# ADIS_Teensy_Arduino_Breakout_RevC.net
KiCad netlist of a schematic drawn in EAGLE
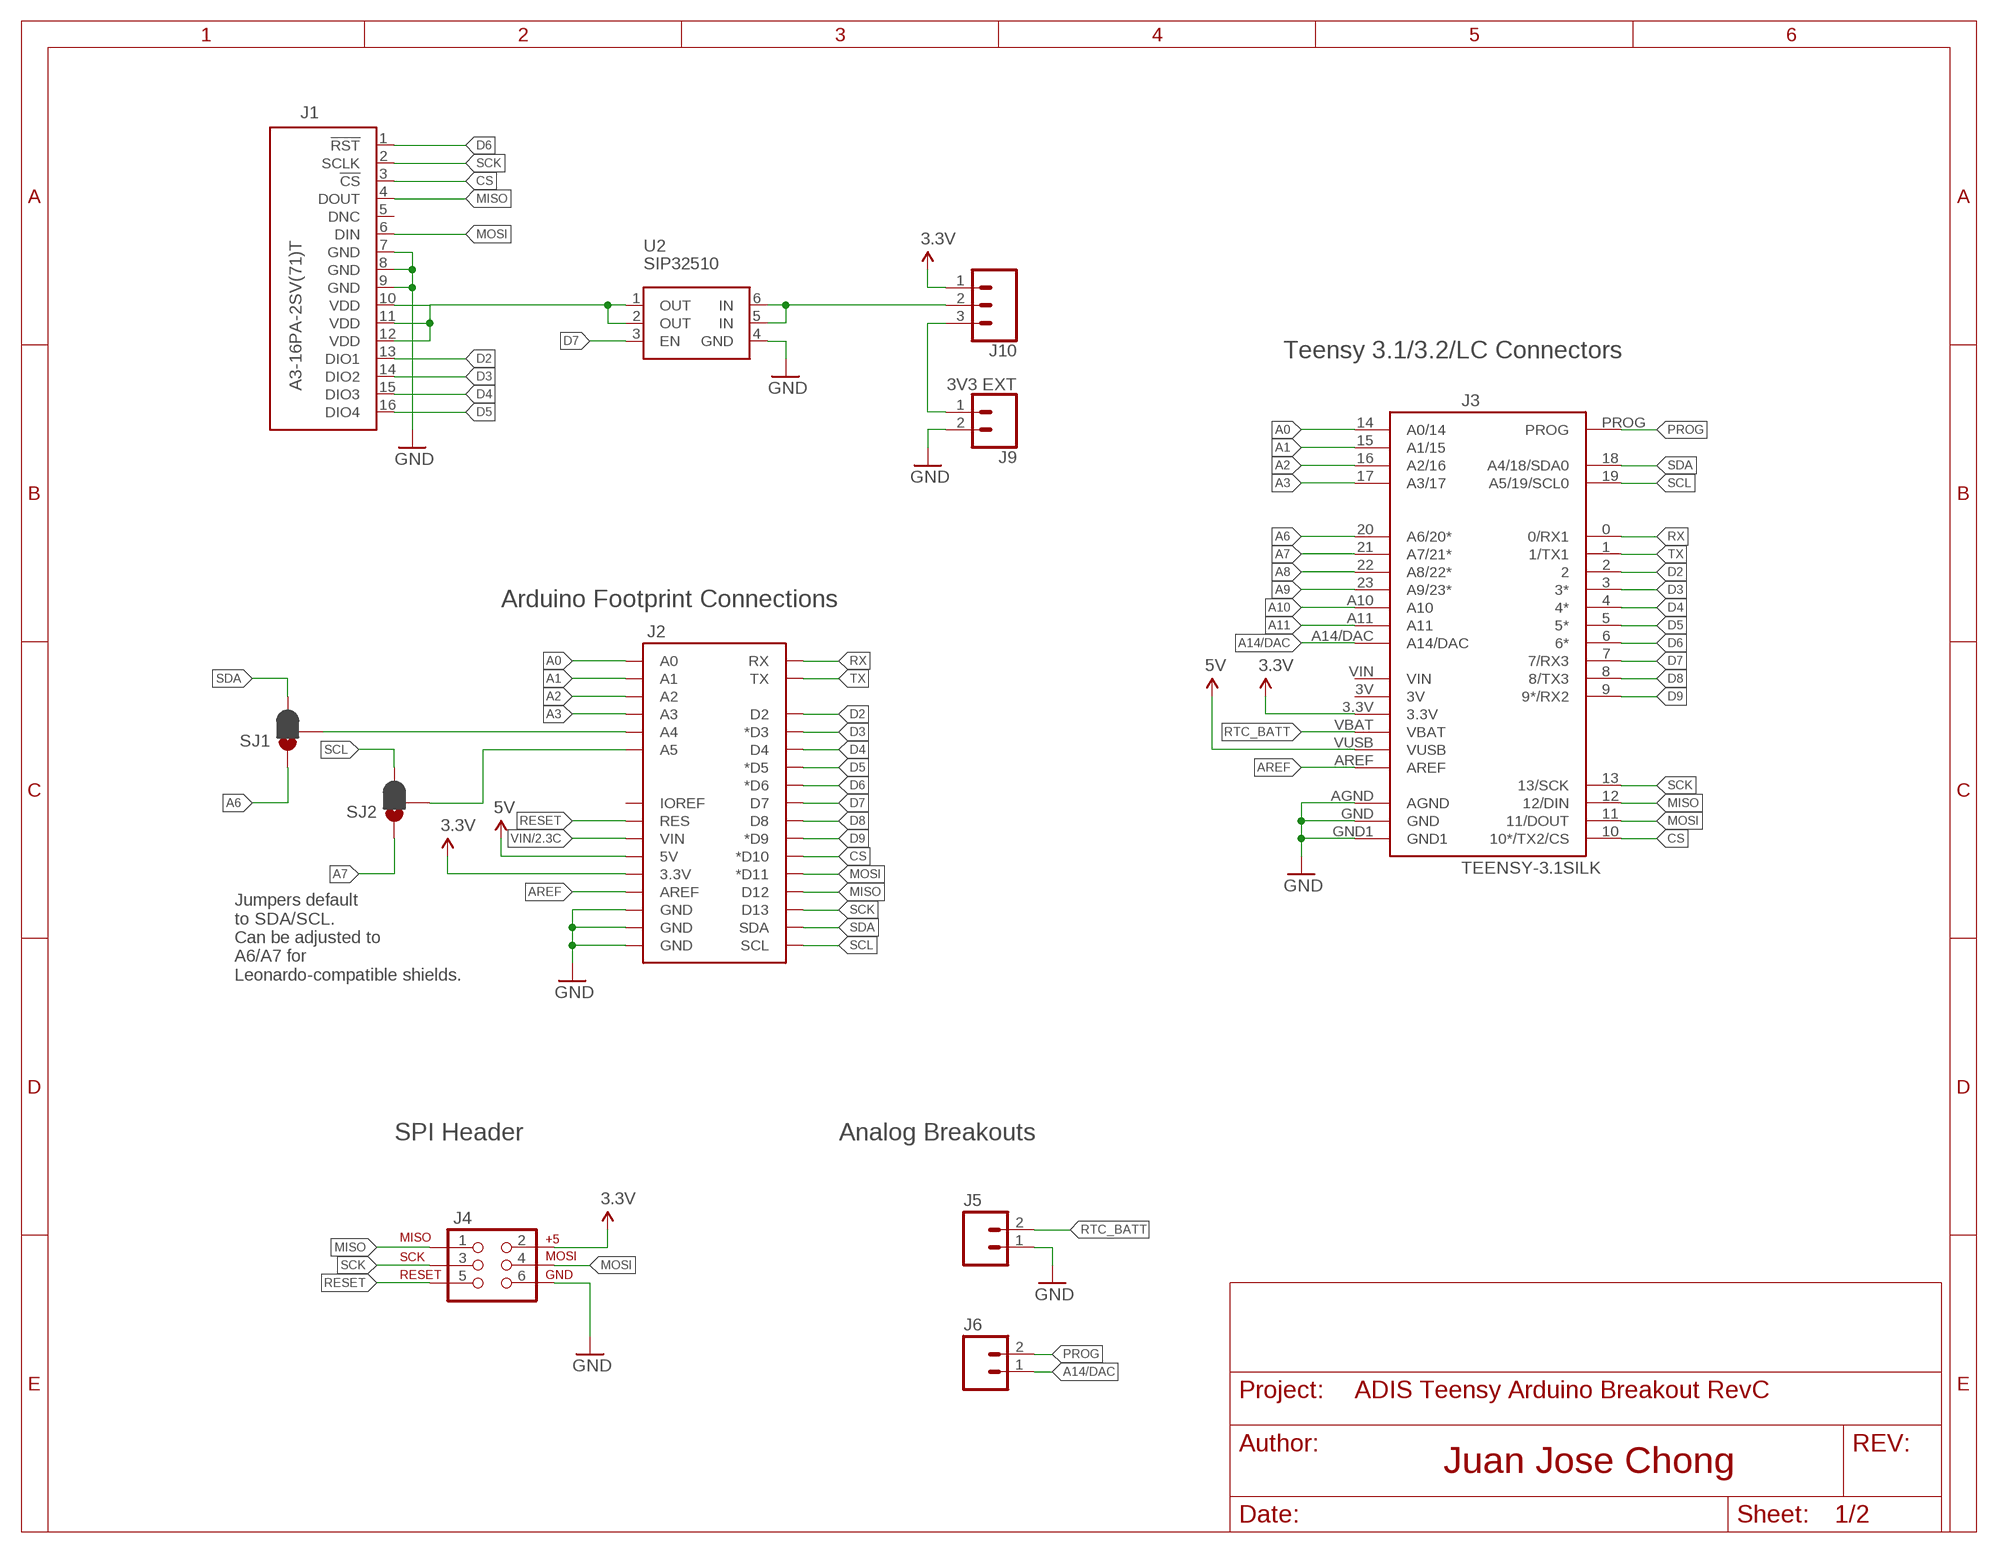
[diagram p0: schematic, sheet 1]
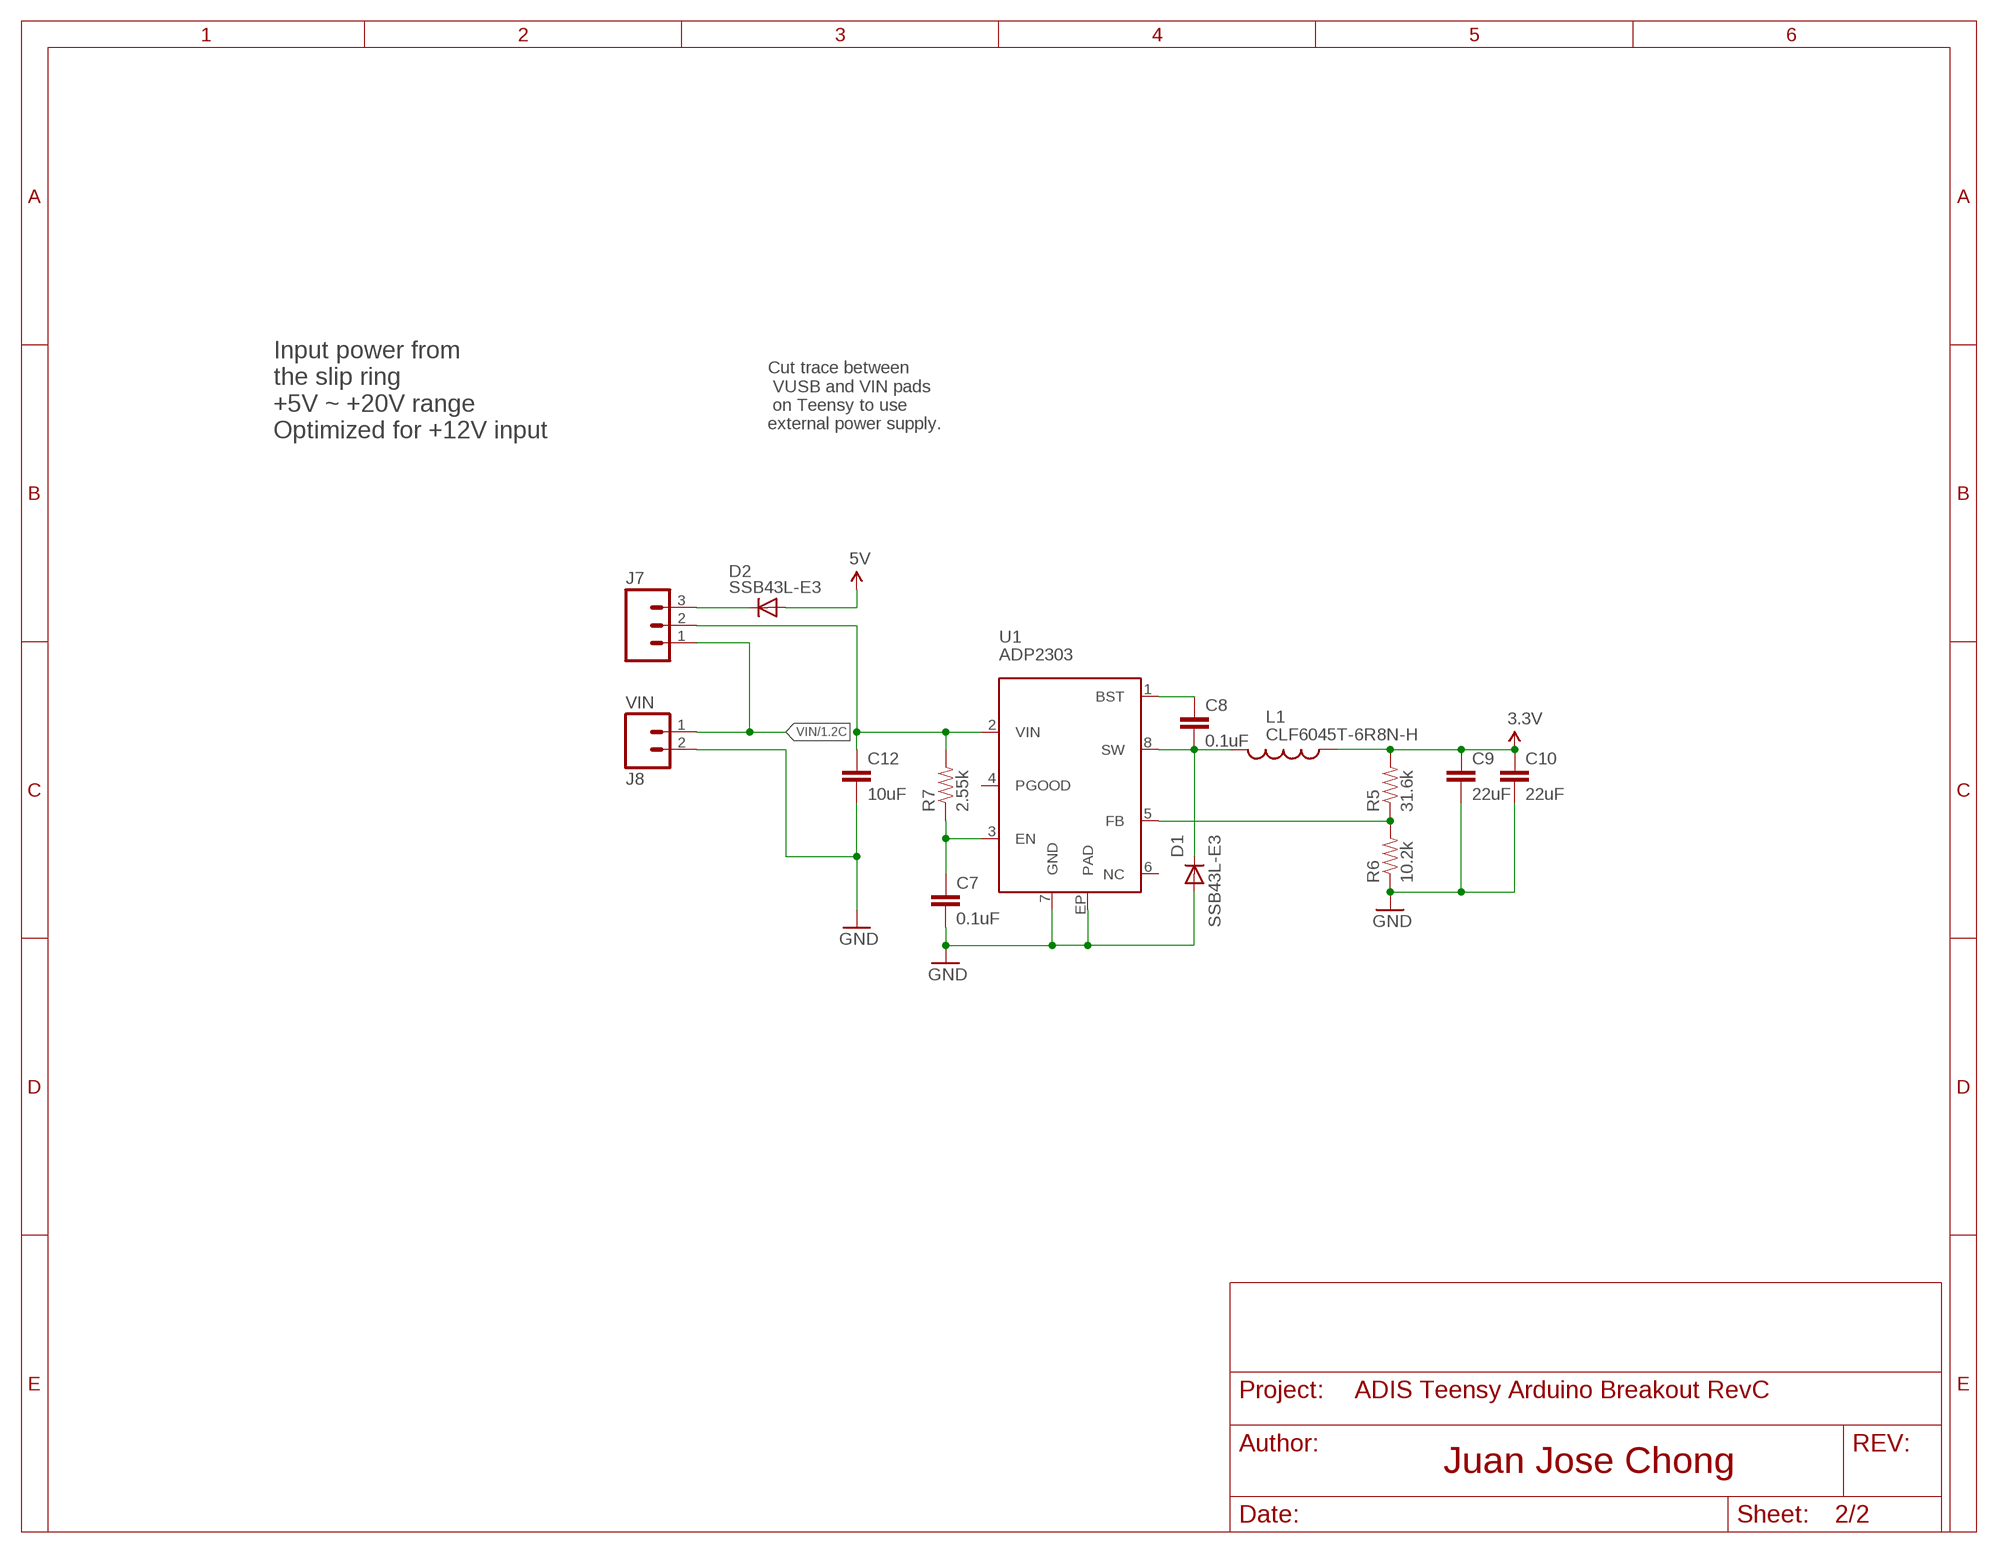
[diagram p1: schematic, sheet 2]

(export (version "E")
  (design (tool "Eeschema 10.0.6"))
  (components
    (comp (ref "C7")
      (value "0.1uF")
      (footprint "eagle-import:0603-CAP")
      (fields (field (name "PARTNO") "CL10B104KB8NNNC"))
      (libsource (lib "eagle-import") (part "CAP0603-CAP"))
    )
    (comp (ref "C8")
      (value "0.1uF")
      (footprint "eagle-import:0603-CAP")
      (fields (field (name "PARTNO") "CL10B104KB8NNNC"))
      (libsource (lib "eagle-import") (part "CAP0603-CAP"))
    )
    (comp (ref "C9")
      (value "22uF")
      (footprint "eagle-import:1210")
      (fields (field (name "PARTNO") "TLJA476M010R0600"))
      (libsource (lib "eagle-import") (part "CAP1210"))
    )
    (comp (ref "C10")
      (value "22uF")
      (footprint "eagle-import:1210")
      (fields (field (name "PARTNO") "TLJA476M010R0600"))
      (libsource (lib "eagle-import") (part "CAP1210"))
    )
    (comp (ref "C12")
      (value "10uF")
      (footprint "eagle-import:1206")
      (fields (field (name "PARTNO") "TLJA476M010R0600"))
      (libsource (lib "eagle-import") (part "CAP1206"))
    )
    (comp (ref "D1")
      (value "SSB43L-E3")
      (footprint "eagle-import:DO214AA")
      (fields (field (name "PARTNO") "SSB43L-E3/52T"))
      (libsource (lib "eagle-import") (part "DIODE-DO214AA"))
    )
    (comp (ref "D2")
      (value "SSB43L-E3")
      (footprint "eagle-import:DO214AA")
      (fields (field (name "PARTNO") "SSB43L-E3/52T"))
      (libsource (lib "eagle-import") (part "DIODE-DO214AA"))
    )
    (comp (ref "J7")
      (value "M03PTH")
      (footprint "eagle-import:1X03@1")
      (fields (field (name "PARTNO") "68000-103HLF"))
      (libsource (lib "eagle-import") (part "M03PTH"))
    )
    (comp (ref "J8")
      (value "VIN")
      (footprint "eagle-import:SCREWTERMINAL-3.5MM-2@1")
      (fields (field (name "PARTNO") "20020327-C021B01LF"))
      (libsource (lib "eagle-import") (part "M023.5MM"))
    )
    (comp (ref "L1")
      (value "CLF6045T-6R8N-H")
      (footprint "eagle-import:CLF6045-H")
      (libsource (lib "eagle-import") (part "CLF6045T-6R8N-H"))
    )
    (comp (ref "R5")
      (value "31.6k")
      (footprint "eagle-import:0603-RES")
      (fields (field (name "PARTNO") "ERJ-3EKF3162V"))
      (libsource (lib "eagle-import") (part "RESISTOR0603-RES"))
    )
    (comp (ref "R6")
      (value "10.2k")
      (footprint "eagle-import:0603-RES")
      (fields (field (name "PARTNO") "ERJ-3EKF1022V"))
      (libsource (lib "eagle-import") (part "RESISTOR0603-RES"))
    )
    (comp (ref "R7")
      (value "2.55k")
      (footprint "eagle-import:0603-RES")
      (fields (field (name "PARTNO") "ERJ-3EKF2551V"))
      (libsource (lib "eagle-import") (part "RESISTOR0603-RES"))
    )
    (comp (ref "U1")
      (value "ADP2303")
      (footprint "eagle-import:SOIC-8-PAD")
      (fields (field (name "PARTNO") "ADP2303ARDZ"))
      (libsource (lib "eagle-import") (part "ADP2303"))
    )
    (comp (ref "J1")
      (value "A3-16PA-2SV(71)T")
      (footprint "eagle-import:A3-16PA-2SV(71)-TOP")
      (fields (field (name "PARTNO") "A3-16PA-2SV(71)"))
      (libsource (lib "eagle-import") (part "A3-16PA-2SV(71)T"))
    )
    (comp (ref "J2")
      (value "ARDUINO_R3_SHIELDUNO_R3_SHIELD_HOLES")
      (footprint "eagle-import:UNO_R3_SHIELD_HOLES")
      (libsource (lib "eagle-import") (part "ARDUINO_R3_SHIELDUNO_R3_SHIELD_HOLES"))
    )
    (comp (ref "J3")
      (value "TEENSY-3.1SILK")
      (footprint "eagle-import:TEENSY-3.1")
      (fields (field (name "PARTNO") "TEENSY32"))
      (libsource (lib "eagle-import") (part "TEENSY-3.1SILK"))
    )
    (comp (ref "J4")
      (value "AVR_SPI_PRG_6PTH")
      (footprint "eagle-import:2X3")
      (fields (field (name "PARTNO") "M20-9720345"))
      (libsource (lib "eagle-import") (part "AVR_SPI_PRG_6PTH"))
    )
    (comp (ref "J5")
      (value "M02PTH")
      (footprint "eagle-import:1X02@1")
      (libsource (lib "eagle-import") (part "M02PTH"))
    )
    (comp (ref "J6")
      (value "M02PTH")
      (footprint "eagle-import:1X02@1")
      (libsource (lib "eagle-import") (part "M02PTH"))
    )
    (comp (ref "J9")
      (value "3V3 EXT")
      (footprint "eagle-import:SCREWTERMINAL-3.5MM-2")
      (fields (field (name "PARTNO") "20020327-C021B01LF"))
      (libsource (lib "eagle-import") (part "CONN_023.5MM"))
    )
    (comp (ref "J10")
      (value "CONN_03")
      (footprint "eagle-import:1X03")
      (fields (field (name "PARTNO") "68000-103HLF"))
      (libsource (lib "eagle-import") (part "CONN_03"))
    )
    (comp (ref "SJ1")
      (value "JUMPER-PAD-3-2OF3_NC_BY_PASTE")
      (footprint "eagle-import:PAD-JUMPER-3-2OF3_NC_BY_PASTE_YES_SILK_FULL_BOX")
      (libsource (lib "eagle-import") (part "JUMPER-PAD-3-2OF3_NC_BY_PASTE"))
    )
    (comp (ref "SJ2")
      (value "JUMPER-PAD-3-2OF3_NC_BY_PASTE")
      (footprint "eagle-import:PAD-JUMPER-3-2OF3_NC_BY_PASTE_YES_SILK_FULL_BOX")
      (libsource (lib "eagle-import") (part "JUMPER-PAD-3-2OF3_NC_BY_PASTE"))
    )
    (comp (ref "U2")
      (value "SIP32510")
      (footprint "eagle-import:SOT23-6")
      (fields (field (name "PARTNO") "SIP32510DT-T1-GE3"))
      (libsource (lib "eagle-import") (part "SIP32510"))
    )
  )
  (nets
    (net (code "1") (name "3.3V") (class "Default")
      (node (ref "C10") (pin "1") (pinfunction "1_1") (pintype "passive"))
      (node (ref "C9") (pin "1") (pinfunction "1_1") (pintype "passive"))
      (node (ref "J10") (pin "1") (pinfunction "1_1") (pintype "passive"))
      (node (ref "J2") (pin "3.3V") (pinfunction "3.3V_3.3V") (pintype "bidirectional"))
      (node (ref "J3") (pin "3.3V") (pinfunction "3.3V_3.3V") (pintype "bidirectional"))
      (node (ref "J4") (pin "2") (pinfunction "2_2") (pintype "passive"))
      (node (ref "L1") (pin "P$1") (pinfunction "1_P$1") (pintype "passive"))
      (node (ref "R5") (pin "2") (pinfunction "2_2") (pintype "passive"))
    )
    (net (code "2") (name "5V") (class "Default")
      (node (ref "D2") (pin "A") (pinfunction "A_A") (pintype "passive"))
      (node (ref "J2") (pin "5V") (pinfunction "5V_5V") (pintype "bidirectional"))
      (node (ref "J3") (pin "VUSB") (pinfunction "VUSB_VUSB") (pintype "bidirectional"))
    )
    (net (code "3") (name "A0") (class "Default")
      (node (ref "J2") (pin "A0") (pinfunction "A0_A0") (pintype "bidirectional"))
      (node (ref "J3") (pin "14") (pinfunction "A0/14_14") (pintype "bidirectional"))
    )
    (net (code "4") (name "A1") (class "Default")
      (node (ref "J2") (pin "A1") (pinfunction "A1_A1") (pintype "bidirectional"))
      (node (ref "J3") (pin "15") (pinfunction "A1/15_15") (pintype "bidirectional"))
    )
    (net (code "5") (name "A2") (class "Default")
      (node (ref "J2") (pin "A2") (pinfunction "A2_A2") (pintype "bidirectional"))
      (node (ref "J3") (pin "16") (pinfunction "A2/16_16") (pintype "bidirectional"))
    )
    (net (code "6") (name "A3") (class "Default")
      (node (ref "J2") (pin "A3") (pinfunction "A3_A3") (pintype "bidirectional"))
      (node (ref "J3") (pin "17") (pinfunction "A3/17_17") (pintype "bidirectional"))
    )
    (net (code "7") (name "A6") (class "Default")
      (node (ref "J3") (pin "20") (pinfunction "A6/20*_20") (pintype "bidirectional"))
      (node (ref "SJ1") (pin "1") (pinfunction "1_1") (pintype "passive"))
    )
    (net (code "8") (name "A7") (class "Default")
      (node (ref "J3") (pin "21") (pinfunction "A7/21*_21") (pintype "bidirectional"))
      (node (ref "SJ2") (pin "1") (pinfunction "1_1") (pintype "passive"))
    )
    (net (code "9") (name "A8") (class "Default")
      (node (ref "J3") (pin "22") (pinfunction "A8/22*_22") (pintype "bidirectional"))
    )
    (net (code "10") (name "A9") (class "Default")
      (node (ref "J3") (pin "23") (pinfunction "A9/23*_23") (pintype "bidirectional"))
    )
    (net (code "11") (name "A10") (class "Default")
      (node (ref "J3") (pin "A10") (pinfunction "A10_A10") (pintype "bidirectional"))
    )
    (net (code "12") (name "A11") (class "Default")
      (node (ref "J3") (pin "A11") (pinfunction "A11_A11") (pintype "bidirectional"))
    )
    (net (code "13") (name "A14{slash}DAC") (class "Default")
      (node (ref "J3") (pin "A14/DAC") (pinfunction "A14/DAC_A14/DAC") (pintype "bidirectional"))
      (node (ref "J6") (pin "1") (pinfunction "1_1") (pintype "passive"))
    )
    (net (code "14") (name "AREF") (class "Default")
      (node (ref "J2") (pin "AREF") (pinfunction "AREF_AREF") (pintype "bidirectional"))
      (node (ref "J3") (pin "AREF") (pinfunction "AREF_AREF") (pintype "bidirectional"))
    )
    (net (code "15") (name "CS") (class "Default")
      (node (ref "J1") (pin "3") (pinfunction "~{CS}_3") (pintype "bidirectional"))
      (node (ref "J2") (pin "D10") (pinfunction "*D10_D10") (pintype "bidirectional"))
      (node (ref "J3") (pin "10") (pinfunction "10*/TX2/CS_10") (pintype "bidirectional"))
    )
    (net (code "16") (name "D2") (class "Default")
      (node (ref "J1") (pin "13") (pinfunction "DIO1_13") (pintype "bidirectional"))
      (node (ref "J2") (pin "D2") (pinfunction "D2_D2") (pintype "bidirectional"))
      (node (ref "J3") (pin "2") (pinfunction "2_2") (pintype "bidirectional"))
    )
    (net (code "17") (name "D3") (class "Default")
      (node (ref "J1") (pin "14") (pinfunction "DIO2_14") (pintype "bidirectional"))
      (node (ref "J2") (pin "D3") (pinfunction "*D3_D3") (pintype "bidirectional"))
      (node (ref "J3") (pin "3") (pinfunction "3*_3") (pintype "bidirectional"))
    )
    (net (code "18") (name "D4") (class "Default")
      (node (ref "J1") (pin "15") (pinfunction "DIO3_15") (pintype "bidirectional"))
      (node (ref "J2") (pin "D4") (pinfunction "D4_D4") (pintype "bidirectional"))
      (node (ref "J3") (pin "4") (pinfunction "4*_4") (pintype "bidirectional"))
    )
    (net (code "19") (name "D5") (class "Default")
      (node (ref "J1") (pin "16") (pinfunction "DIO4_16") (pintype "bidirectional"))
      (node (ref "J2") (pin "D5") (pinfunction "*D5_D5") (pintype "bidirectional"))
      (node (ref "J3") (pin "5") (pinfunction "5*_5") (pintype "bidirectional"))
    )
    (net (code "20") (name "D6") (class "Default")
      (node (ref "J1") (pin "1") (pinfunction "~{RST}_1") (pintype "bidirectional"))
      (node (ref "J2") (pin "D6") (pinfunction "*D6_D6") (pintype "bidirectional"))
      (node (ref "J3") (pin "6") (pinfunction "6*_6") (pintype "bidirectional"))
    )
    (net (code "21") (name "D7") (class "Default")
      (node (ref "J2") (pin "D7") (pinfunction "D7_D7") (pintype "bidirectional"))
      (node (ref "J3") (pin "7") (pinfunction "7/RX3_7") (pintype "bidirectional"))
      (node (ref "U2") (pin "3") (pinfunction "EN_3") (pintype "bidirectional"))
    )
    (net (code "22") (name "D8") (class "Default")
      (node (ref "J2") (pin "D8") (pinfunction "D8_D8") (pintype "bidirectional"))
      (node (ref "J3") (pin "8") (pinfunction "8/TX3_8") (pintype "bidirectional"))
    )
    (net (code "23") (name "D9") (class "Default")
      (node (ref "J2") (pin "D9") (pinfunction "*D9_D9") (pintype "bidirectional"))
      (node (ref "J3") (pin "9") (pinfunction "9*/RX2_9") (pintype "bidirectional"))
    )
    (net (code "24") (name "GND") (class "Default")
      (node (ref "C10") (pin "2") (pinfunction "2_2") (pintype "passive"))
      (node (ref "C12") (pin "2") (pinfunction "2_2") (pintype "passive"))
      (node (ref "C7") (pin "2") (pinfunction "2_2") (pintype "passive"))
      (node (ref "C9") (pin "2") (pinfunction "2_2") (pintype "passive"))
      (node (ref "D1") (pin "A") (pinfunction "A_A") (pintype "passive"))
      (node (ref "J1") (pin "7") (pinfunction "GND_7") (pintype "bidirectional"))
      (node (ref "J1") (pin "8") (pinfunction "GND_8") (pintype "bidirectional"))
      (node (ref "J1") (pin "9") (pinfunction "GND_9") (pintype "bidirectional"))
      (node (ref "J2") (pin "GND@0") (pinfunction "GND_GND@0") (pintype "bidirectional"))
      (node (ref "J2") (pin "GND@1") (pinfunction "GND_GND@1") (pintype "bidirectional"))
      (node (ref "J2") (pin "GND@2") (pinfunction "GND_GND@2") (pintype "bidirectional"))
      (node (ref "J3") (pin "AGND") (pinfunction "AGND_AGND") (pintype "bidirectional"))
      (node (ref "J3") (pin "GND") (pinfunction "GND_GND") (pintype "bidirectional"))
      (node (ref "J3") (pin "GND1") (pinfunction "GND1_GND1") (pintype "bidirectional"))
      (node (ref "J4") (pin "6") (pinfunction "6_6") (pintype "passive"))
      (node (ref "J5") (pin "1") (pinfunction "1_1") (pintype "passive"))
      (node (ref "J8") (pin "2") (pinfunction "2_2") (pintype "passive"))
      (node (ref "J9") (pin "2") (pinfunction "2_2") (pintype "passive"))
      (node (ref "R6") (pin "1") (pinfunction "1_1") (pintype "passive"))
      (node (ref "U1") (pin "7") (pinfunction "GND_7") (pintype "bidirectional"))
      (node (ref "U1") (pin "EP") (pinfunction "PAD_EP") (pintype "bidirectional"))
      (node (ref "U2") (pin "4") (pinfunction "GND_4") (pintype "bidirectional"))
    )
    (net (code "25") (name "MISO") (class "Default")
      (node (ref "J1") (pin "4") (pinfunction "DOUT_4") (pintype "bidirectional"))
      (node (ref "J2") (pin "D12") (pinfunction "D12_D12") (pintype "bidirectional"))
      (node (ref "J3") (pin "12") (pinfunction "12/DIN_12") (pintype "bidirectional"))
      (node (ref "J4") (pin "1") (pinfunction "1_1") (pintype "passive"))
    )
    (net (code "26") (name "MOSI") (class "Default")
      (node (ref "J1") (pin "6") (pinfunction "DIN_6") (pintype "bidirectional"))
      (node (ref "J2") (pin "D11") (pinfunction "*D11_D11") (pintype "bidirectional"))
      (node (ref "J3") (pin "11") (pinfunction "11/DOUT_11") (pintype "bidirectional"))
      (node (ref "J4") (pin "4") (pinfunction "4_4") (pintype "passive"))
    )
    (net (code "27") (name "Net-(D2-PadC)") (class "Default")
      (node (ref "D2") (pin "C") (pinfunction "C_C") (pintype "passive"))
      (node (ref "J7") (pin "3") (pinfunction "3_3") (pintype "passive"))
    )
    (net (code "28") (name "Net-(J1-VDD-Pad10)") (class "Default")
      (node (ref "J1") (pin "10") (pinfunction "VDD_10") (pintype "bidirectional"))
      (node (ref "J1") (pin "11") (pinfunction "VDD_11") (pintype "bidirectional"))
      (node (ref "J1") (pin "12") (pinfunction "VDD_12") (pintype "bidirectional"))
      (node (ref "U2") (pin "1") (pinfunction "OUT_1") (pintype "bidirectional"))
      (node (ref "U2") (pin "2") (pinfunction "OUT_2") (pintype "bidirectional"))
    )
    (net (code "29") (name "Net-(J2-PadA4)") (class "Default")
      (node (ref "J2") (pin "A4") (pinfunction "A4_A4") (pintype "bidirectional"))
      (node (ref "SJ1") (pin "2") (pinfunction "2_2") (pintype "passive"))
    )
    (net (code "30") (name "Net-(J2-PadA5)") (class "Default")
      (node (ref "J2") (pin "A5") (pinfunction "A5_A5") (pintype "bidirectional"))
      (node (ref "SJ2") (pin "2") (pinfunction "2_2") (pintype "passive"))
    )
    (net (code "31") (name "Net-(J10-Pad2)") (class "Default")
      (node (ref "J10") (pin "2") (pinfunction "2_2") (pintype "passive"))
      (node (ref "U2") (pin "5") (pinfunction "IN_5") (pintype "bidirectional"))
      (node (ref "U2") (pin "6") (pinfunction "IN_6") (pintype "bidirectional"))
    )
    (net (code "32") (name "Net-(J10-Pad3)") (class "Default")
      (node (ref "J10") (pin "3") (pinfunction "3_3") (pintype "passive"))
      (node (ref "J9") (pin "1") (pinfunction "1_1") (pintype "passive"))
    )
    (net (code "33") (name "Net-(L1-2)") (class "Default")
      (node (ref "C8") (pin "2") (pinfunction "2_2") (pintype "passive"))
      (node (ref "D1") (pin "C") (pinfunction "C_C") (pintype "passive"))
      (node (ref "L1") (pin "P$2") (pinfunction "2_P$2") (pintype "passive"))
      (node (ref "U1") (pin "8") (pinfunction "SW_8") (pintype "bidirectional"))
    )
    (net (code "34") (name "Net-(U1-BST)") (class "Default")
      (node (ref "C8") (pin "1") (pinfunction "1_1") (pintype "passive"))
      (node (ref "U1") (pin "1") (pinfunction "BST_1") (pintype "bidirectional"))
    )
    (net (code "35") (name "Net-(U1-EN)") (class "Default")
      (node (ref "C7") (pin "1") (pinfunction "1_1") (pintype "passive"))
      (node (ref "R7") (pin "1") (pinfunction "1_1") (pintype "passive"))
      (node (ref "U1") (pin "3") (pinfunction "EN_3") (pintype "bidirectional"))
    )
    (net (code "36") (name "Net-(U1-FB)") (class "Default")
      (node (ref "R5") (pin "1") (pinfunction "1_1") (pintype "passive"))
      (node (ref "R6") (pin "2") (pinfunction "2_2") (pintype "passive"))
      (node (ref "U1") (pin "5") (pinfunction "FB_5") (pintype "bidirectional"))
    )
    (net (code "37") (name "Net-(U1-VIN)") (class "Default")
      (node (ref "C12") (pin "1") (pinfunction "1_1") (pintype "passive"))
      (node (ref "J7") (pin "2") (pinfunction "2_2") (pintype "passive"))
      (node (ref "R7") (pin "2") (pinfunction "2_2") (pintype "passive"))
      (node (ref "U1") (pin "2") (pinfunction "VIN_2") (pintype "bidirectional"))
    )
    (net (code "38") (name "PROG") (class "Default")
      (node (ref "J3") (pin "PROG") (pinfunction "PROG_PROG") (pintype "bidirectional"))
      (node (ref "J6") (pin "2") (pinfunction "2_2") (pintype "passive"))
    )
    (net (code "39") (name "RESET") (class "Default")
      (node (ref "J2") (pin "RES") (pinfunction "RES_RES") (pintype "bidirectional"))
      (node (ref "J4") (pin "5") (pinfunction "5_5") (pintype "passive"))
    )
    (net (code "40") (name "RTC_BATT") (class "Default")
      (node (ref "J3") (pin "VBAT") (pinfunction "VBAT_VBAT") (pintype "bidirectional"))
      (node (ref "J5") (pin "2") (pinfunction "2_2") (pintype "passive"))
    )
    (net (code "41") (name "RX") (class "Default")
      (node (ref "J2") (pin "RX") (pinfunction "RX_RX") (pintype "bidirectional"))
      (node (ref "J3") (pin "0") (pinfunction "0/RX1_0") (pintype "bidirectional"))
    )
    (net (code "42") (name "SCK") (class "Default")
      (node (ref "J1") (pin "2") (pinfunction "SCLK_2") (pintype "bidirectional"))
      (node (ref "J2") (pin "D13") (pinfunction "D13_D13") (pintype "bidirectional"))
      (node (ref "J3") (pin "13") (pinfunction "13/SCK_13") (pintype "bidirectional"))
      (node (ref "J4") (pin "3") (pinfunction "3_3") (pintype "passive"))
    )
    (net (code "43") (name "SCL") (class "Default")
      (node (ref "J2") (pin "SCL") (pinfunction "SCL_SCL") (pintype "bidirectional"))
      (node (ref "J3") (pin "19") (pinfunction "A5/19/SCL0_19") (pintype "bidirectional"))
      (node (ref "SJ2") (pin "3") (pinfunction "3_3") (pintype "passive"))
    )
    (net (code "44") (name "SDA") (class "Default")
      (node (ref "J2") (pin "SDA") (pinfunction "SDA_SDA") (pintype "bidirectional"))
      (node (ref "J3") (pin "18") (pinfunction "A4/18/SDA0_18") (pintype "bidirectional"))
      (node (ref "SJ1") (pin "3") (pinfunction "3_3") (pintype "passive"))
    )
    (net (code "45") (name "TX") (class "Default")
      (node (ref "J2") (pin "TX") (pinfunction "TX_TX") (pintype "bidirectional"))
      (node (ref "J3") (pin "1") (pinfunction "1/TX1_1") (pintype "bidirectional"))
    )
    (net (code "46") (name "VIN") (class "Default")
      (node (ref "J2") (pin "VIN") (pinfunction "VIN_VIN") (pintype "bidirectional"))
      (node (ref "J7") (pin "1") (pinfunction "1_1") (pintype "passive"))
      (node (ref "J8") (pin "1") (pinfunction "1_1") (pintype "passive"))
    )
    (net (code "47") (name "unconnected-(J1-DNC-Pad5)") (class "Default")
      (node (ref "J1") (pin "5") (pinfunction "DNC_5") (pintype "bidirectional"))
    )
    (net (code "48") (name "unconnected-(J2-PadIOREF)") (class "Default")
      (node (ref "J2") (pin "IOREF") (pinfunction "IOREF_IOREF") (pintype "bidirectional"))
    )
    (net (code "49") (name "unconnected-(J3-Pad3V)") (class "Default")
      (node (ref "J3") (pin "3V") (pinfunction "3V_3V") (pintype "bidirectional"))
    )
    (net (code "50") (name "unconnected-(J3-PadVIN)") (class "Default")
      (node (ref "J3") (pin "VIN") (pinfunction "VIN_VIN") (pintype "bidirectional"))
    )
    (net (code "51") (name "unconnected-(U1-NC-Pad6)") (class "Default")
      (node (ref "U1") (pin "6") (pinfunction "NC_6") (pintype "bidirectional"))
    )
    (net (code "52") (name "unconnected-(U1-PGOOD-Pad4)") (class "Default")
      (node (ref "U1") (pin "4") (pinfunction "PGOOD_4") (pintype "bidirectional"))
    )
  )
)
